# POWER.net
KiCad netlist of a schematic drawn in Altium Designer
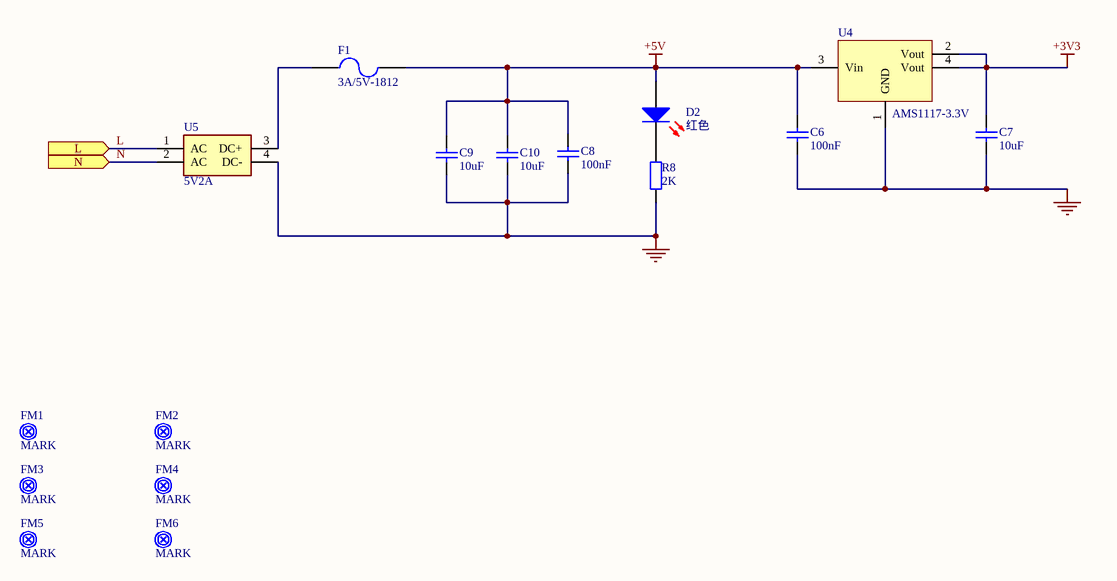
[diagram p0: POWER.SchDoc]

(export (version "E")
  (design (tool "Eeschema 10.0.6"))
  (components
    (comp (ref "C6")
      (value "100nF")
      (footprint "C0603")
      (description "Capacitor")
      (libsource (lib "贴片电容") (part "100nF_50V_0603"))
    )
    (comp (ref "C7")
      (value "10uF")
      (footprint "C0603")
      (description "Capacitor")
      (libsource (lib "贴片电容") (part "10uF_16V_0603"))
    )
    (comp (ref "C8")
      (value "100nF")
      (footprint "C0603")
      (description "Capacitor")
      (libsource (lib "贴片电容") (part "100nF_50V_0603"))
    )
    (comp (ref "C9")
      (value "10uF")
      (footprint "C0603")
      (description "Capacitor")
      (libsource (lib "贴片电容") (part "10uF_16V_0603"))
    )
    (comp (ref "C10")
      (value "10uF")
      (footprint "C0603")
      (description "Capacitor")
      (libsource (lib "贴片电容") (part "10uF_16V_0603"))
    )
    (comp (ref "D2")
      (value "红色")
      (footprint "LED0805-R")
      (description "0805 LED")
      (libsource (lib "二极管") (part "LED-0805-红"))
    )
    (comp (ref "F1")
      (value "3A/5V-1812")
      (footprint "F1812")
      (description "3A/5V")
      (libsource (lib "杂项元件") (part "Fuse-3A/5V-1812"))
    )
    (comp (ref "FM1")
      (value "MARK")
      (footprint "FIDUCAL_MARK")
      (description "MARK标志")
      (libsource (lib "杂项元件") (part "FIDUCIAL_MARK"))
    )
    (comp (ref "FM2")
      (value "MARK")
      (footprint "FIDUCAL_MARK")
      (description "MARK标志")
      (libsource (lib "杂项元件") (part "FIDUCIAL_MARK"))
    )
    (comp (ref "FM3")
      (value "MARK")
      (footprint "FIDUCAL_MARK")
      (description "MARK标志")
      (libsource (lib "杂项元件") (part "FIDUCIAL_MARK"))
    )
    (comp (ref "FM4")
      (value "MARK")
      (footprint "FIDUCAL_MARK")
      (description "MARK标志")
      (libsource (lib "杂项元件") (part "FIDUCIAL_MARK"))
    )
    (comp (ref "FM5")
      (value "MARK")
      (footprint "FIDUCAL_MARK")
      (description "MARK标志")
      (libsource (lib "杂项元件") (part "FIDUCIAL_MARK"))
    )
    (comp (ref "FM6")
      (value "MARK")
      (footprint "FIDUCAL_MARK")
      (description "MARK标志")
      (libsource (lib "杂项元件") (part "FIDUCIAL_MARK"))
    )
    (comp (ref "R8")
      (value "2K")
      (footprint "R0603")
      (description "2K,±5%,0603")
      (libsource (lib "贴片电阻") (part "2K_5%_0603"))
    )
    (comp (ref "U4")
      (value "AMS1117-3.3V")
      (footprint "SOT-223")
      (description "三端稳压")
      (libsource (lib "IC-GTA") (part "AMS1117-3.3V-SOT223"))
    )
    (comp (ref "U5")
      (value "5V2A")
      (footprint "Module_RPD10W")
      (description "AC/DC模块")
      (libsource (lib "杂项元件") (part "Module_RPD10W05E202S"))
    )
  )
  (nets
    (net (code "1") (name "+3V3") (class "Default")
      (node (ref "C7") (pin "2") (pinfunction "2_2") (pintype "passive"))
      (node (ref "U4") (pin "2") (pinfunction "Vout_2") (pintype "passive"))
      (node (ref "U4") (pin "4") (pinfunction "Vout_4") (pintype "passive"))
    )
    (net (code "2") (name "+5V") (class "Default")
      (node (ref "C10") (pin "2") (pinfunction "2_2") (pintype "passive"))
      (node (ref "C6") (pin "2") (pinfunction "2_2") (pintype "passive"))
      (node (ref "C8") (pin "2") (pinfunction "2_2") (pintype "passive"))
      (node (ref "C9") (pin "2") (pinfunction "2_2") (pintype "passive"))
      (node (ref "D2") (pin "1") (pinfunction "A_1") (pintype "passive"))
      (node (ref "F1") (pin "2") (pinfunction "2_2") (pintype "passive"))
      (node (ref "U4") (pin "3") (pinfunction "Vin_3") (pintype "passive"))
    )
    (net (code "3") (name "/L") (class "Default")
      (node (ref "U5") (pin "1") (pinfunction "AC_1") (pintype "passive"))
    )
    (net (code "4") (name "/N") (class "Default")
      (node (ref "U5") (pin "2") (pinfunction "AC_2") (pintype "passive"))
    )
    (net (code "5") (name "GND") (class "Default")
      (node (ref "C10") (pin "1") (pinfunction "1_1") (pintype "passive"))
      (node (ref "C6") (pin "1") (pinfunction "1_1") (pintype "passive"))
      (node (ref "C7") (pin "1") (pinfunction "1_1") (pintype "passive"))
      (node (ref "C8") (pin "1") (pinfunction "1_1") (pintype "passive"))
      (node (ref "C9") (pin "1") (pinfunction "1_1") (pintype "passive"))
      (node (ref "R8") (pin "1") (pinfunction "1_1") (pintype "passive"))
      (node (ref "U4") (pin "1") (pinfunction "GND_1") (pintype "passive"))
      (node (ref "U5") (pin "4") (pinfunction "DC-_4") (pintype "passive"))
    )
    (net (code "6") (name "Net-(D2-K)") (class "Default")
      (node (ref "D2") (pin "2") (pinfunction "K_2") (pintype "passive"))
      (node (ref "R8") (pin "2") (pinfunction "2_2") (pintype "passive"))
    )
    (net (code "7") (name "Net-(U5-DC+)") (class "Default")
      (node (ref "F1") (pin "1") (pinfunction "1_1") (pintype "passive"))
      (node (ref "U5") (pin "3") (pinfunction "DC+_3") (pintype "passive"))
    )
    (net (code "8") (name "unconnected-(FM1-Pad1)") (class "Default")
      (node (ref "FM1") (pin "1") (pinfunction "1_1") (pintype "passive"))
    )
    (net (code "9") (name "unconnected-(FM2-Pad1)") (class "Default")
      (node (ref "FM2") (pin "1") (pinfunction "1_1") (pintype "passive"))
    )
    (net (code "10") (name "unconnected-(FM3-Pad1)") (class "Default")
      (node (ref "FM3") (pin "1") (pinfunction "1_1") (pintype "passive"))
    )
    (net (code "11") (name "unconnected-(FM4-Pad1)") (class "Default")
      (node (ref "FM4") (pin "1") (pinfunction "1_1") (pintype "passive"))
    )
    (net (code "12") (name "unconnected-(FM5-Pad1)") (class "Default")
      (node (ref "FM5") (pin "1") (pinfunction "1_1") (pintype "passive"))
    )
    (net (code "13") (name "unconnected-(FM6-Pad1)") (class "Default")
      (node (ref "FM6") (pin "1") (pinfunction "1_1") (pintype "passive"))
    )
  )
)
